# design.net
KiCad netlist of a schematic drawn in Altium Designer
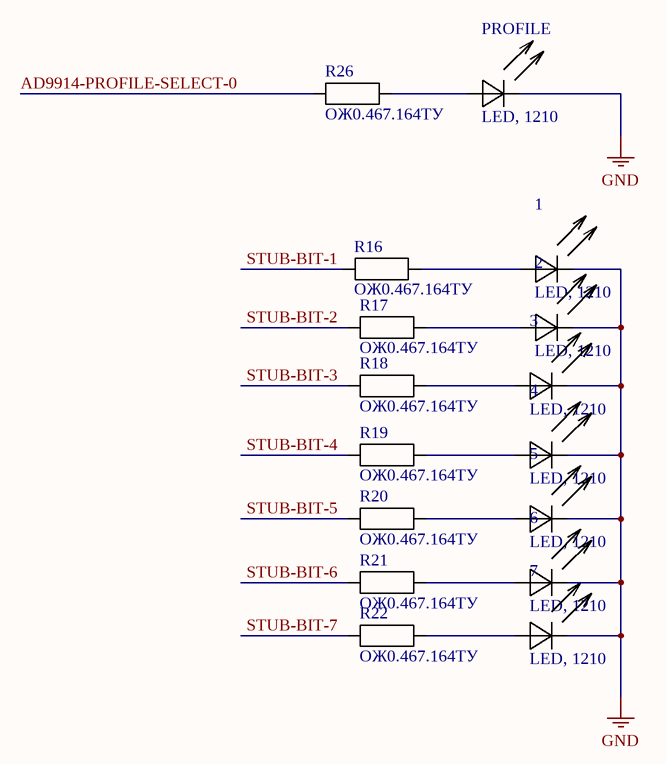
[diagram p0: Светодиоды.SchDoc]

(export (version "E")
  (design (tool "Eeschema 10.0.6"))
  (components
    (comp (ref "1")
      (value "LED, 1210")
      (footprint "PLCC4-1210")
      (fields (field (name "MANUFACTURERPARTNUMBER") "1210 LED"))
      (libsource (lib "ДИОДЫ") (part "1210 LED"))
    )
    (comp (ref "2")
      (value "LED, 1210")
      (footprint "PLCC4-1210")
      (fields (field (name "MANUFACTURERPARTNUMBER") "1210 LED"))
      (libsource (lib "ДИОДЫ") (part "1210 LED"))
    )
    (comp (ref "3")
      (value "LED, 1210")
      (footprint "PLCC4-1210")
      (fields (field (name "MANUFACTURERPARTNUMBER") "1210 LED"))
      (libsource (lib "ДИОДЫ") (part "1210 LED"))
    )
    (comp (ref "4")
      (value "LED, 1210")
      (footprint "PLCC4-1210")
      (fields (field (name "MANUFACTURERPARTNUMBER") "1210 LED"))
      (libsource (lib "ДИОДЫ") (part "1210 LED"))
    )
    (comp (ref "5")
      (value "LED, 1210")
      (footprint "PLCC4-1210")
      (fields (field (name "MANUFACTURERPARTNUMBER") "1210 LED"))
      (libsource (lib "ДИОДЫ") (part "1210 LED"))
    )
    (comp (ref "6")
      (value "LED, 1210")
      (footprint "PLCC4-1210")
      (fields (field (name "MANUFACTURERPARTNUMBER") "1210 LED"))
      (libsource (lib "ДИОДЫ") (part "1210 LED"))
    )
    (comp (ref "7")
      (value "LED, 1210")
      (footprint "PLCC4-1210")
      (fields (field (name "MANUFACTURERPARTNUMBER") "1210 LED"))
      (libsource (lib "ДИОДЫ") (part "1210 LED"))
    )
    (comp (ref "PROFILE")
      (value "LED, 1210")
      (footprint "PLCC4-1210")
      (fields (field (name "MANUFACTURERPARTNUMBER") "1210 LED"))
      (libsource (lib "ДИОДЫ") (part "1210 LED"))
    )
    (comp (ref "R16")
      (value "ОЖ0.467.164ТУ")
      (footprint "Р1-8МП-0,125")
      (fields
        (field (name "TOLERANCE") "±1%-0,5-Л")
        (field (name "MANUFACTURERPARTNUMBER") "Р1-8МП-0,125-100 Ом±1%-0,5-Л")
      )
      (libsource (lib "РЕЗИСТОРЫ") (part "Р1-8МП-0,125-100 Ом±1%"))
    )
    (comp (ref "R17")
      (value "ОЖ0.467.164ТУ")
      (footprint "Р1-8МП-0,125")
      (fields
        (field (name "TOLERANCE") "±1%-0,5-Л")
        (field (name "MANUFACTURERPARTNUMBER") "Р1-8МП-0,125-100 Ом±1%-0,5-Л")
      )
      (libsource (lib "РЕЗИСТОРЫ") (part "Р1-8МП-0,125-100 Ом±1%"))
    )
    (comp (ref "R18")
      (value "ОЖ0.467.164ТУ")
      (footprint "Р1-8МП-0,125")
      (fields
        (field (name "TOLERANCE") "±1%-0,5-Л")
        (field (name "MANUFACTURERPARTNUMBER") "Р1-8МП-0,125-100 Ом±1%-0,5-Л")
      )
      (libsource (lib "РЕЗИСТОРЫ") (part "Р1-8МП-0,125-100 Ом±1%"))
    )
    (comp (ref "R19")
      (value "ОЖ0.467.164ТУ")
      (footprint "Р1-8МП-0,125")
      (fields
        (field (name "TOLERANCE") "±1%-0,5-Л")
        (field (name "MANUFACTURERPARTNUMBER") "Р1-8МП-0,125-100 Ом±1%-0,5-Л")
      )
      (libsource (lib "РЕЗИСТОРЫ") (part "Р1-8МП-0,125-100 Ом±1%"))
    )
    (comp (ref "R20")
      (value "ОЖ0.467.164ТУ")
      (footprint "Р1-8МП-0,125")
      (fields
        (field (name "TOLERANCE") "±1%-0,5-Л")
        (field (name "MANUFACTURERPARTNUMBER") "Р1-8МП-0,125-100 Ом±1%-0,5-Л")
      )
      (libsource (lib "РЕЗИСТОРЫ") (part "Р1-8МП-0,125-100 Ом±1%"))
    )
    (comp (ref "R21")
      (value "ОЖ0.467.164ТУ")
      (footprint "Р1-8МП-0,125")
      (fields
        (field (name "TOLERANCE") "±1%-0,5-Л")
        (field (name "MANUFACTURERPARTNUMBER") "Р1-8МП-0,125-100 Ом±1%-0,5-Л")
      )
      (libsource (lib "РЕЗИСТОРЫ") (part "Р1-8МП-0,125-100 Ом±1%"))
    )
    (comp (ref "R22")
      (value "ОЖ0.467.164ТУ")
      (footprint "Р1-8МП-0,125")
      (fields
        (field (name "TOLERANCE") "±1%-0,5-Л")
        (field (name "MANUFACTURERPARTNUMBER") "Р1-8МП-0,125-100 Ом±1%-0,5-Л")
      )
      (libsource (lib "РЕЗИСТОРЫ") (part "Р1-8МП-0,125-100 Ом±1%"))
    )
    (comp (ref "R26")
      (value "ОЖ0.467.164ТУ")
      (footprint "Р1-8МП-0,125")
      (fields
        (field (name "TOLERANCE") "±1%-0,5-Л")
        (field (name "MANUFACTURERPARTNUMBER") "Р1-8МП-0,125-100 Ом±1%-0,5-Л")
      )
      (libsource (lib "РЕЗИСТОРЫ") (part "Р1-8МП-0,125-100 Ом±1%"))
    )
  )
  (nets
    (net (code "1") (name "/AD9914-PROFILE-SELECT-0") (class "Default")
      (node (ref "R26") (pin "1") (pinfunction "1_1") (pintype "passive"))
    )
    (net (code "2") (name "/STUB-BIT-1") (class "Default")
      (node (ref "R16") (pin "1") (pinfunction "1_1") (pintype "passive"))
    )
    (net (code "3") (name "/STUB-BIT-2") (class "Default")
      (node (ref "R17") (pin "1") (pinfunction "1_1") (pintype "passive"))
    )
    (net (code "4") (name "/STUB-BIT-3") (class "Default")
      (node (ref "R18") (pin "1") (pinfunction "1_1") (pintype "passive"))
    )
    (net (code "5") (name "/STUB-BIT-4") (class "Default")
      (node (ref "R19") (pin "1") (pinfunction "1_1") (pintype "passive"))
    )
    (net (code "6") (name "/STUB-BIT-5") (class "Default")
      (node (ref "R20") (pin "1") (pinfunction "1_1") (pintype "passive"))
    )
    (net (code "7") (name "/STUB-BIT-6") (class "Default")
      (node (ref "R21") (pin "1") (pinfunction "1_1") (pintype "passive"))
    )
    (net (code "8") (name "/STUB-BIT-7") (class "Default")
      (node (ref "R22") (pin "1") (pinfunction "1_1") (pintype "passive"))
    )
    (net (code "9") (name "GND") (class "Default")
      (node (ref "1") (pin "2") (pinfunction "2_2") (pintype "passive"))
      (node (ref "2") (pin "2") (pinfunction "2_2") (pintype "passive"))
      (node (ref "3") (pin "2") (pinfunction "2_2") (pintype "passive"))
      (node (ref "4") (pin "2") (pinfunction "2_2") (pintype "passive"))
      (node (ref "5") (pin "2") (pinfunction "2_2") (pintype "passive"))
      (node (ref "6") (pin "2") (pinfunction "2_2") (pintype "passive"))
      (node (ref "7") (pin "2") (pinfunction "2_2") (pintype "passive"))
      (node (ref "PROFILE") (pin "2") (pinfunction "2_2") (pintype "passive"))
    )
    (net (code "10") (name "Net-(1-Pad1)") (class "Default")
      (node (ref "1") (pin "1") (pinfunction "1_1") (pintype "passive"))
      (node (ref "R16") (pin "2") (pinfunction "2_2") (pintype "passive"))
    )
    (net (code "11") (name "Net-(2-Pad1)") (class "Default")
      (node (ref "2") (pin "1") (pinfunction "1_1") (pintype "passive"))
      (node (ref "R17") (pin "2") (pinfunction "2_2") (pintype "passive"))
    )
    (net (code "12") (name "Net-(3-Pad1)") (class "Default")
      (node (ref "3") (pin "1") (pinfunction "1_1") (pintype "passive"))
      (node (ref "R18") (pin "2") (pinfunction "2_2") (pintype "passive"))
    )
    (net (code "13") (name "Net-(4-Pad1)") (class "Default")
      (node (ref "4") (pin "1") (pinfunction "1_1") (pintype "passive"))
      (node (ref "R19") (pin "2") (pinfunction "2_2") (pintype "passive"))
    )
    (net (code "14") (name "Net-(5-Pad1)") (class "Default")
      (node (ref "5") (pin "1") (pinfunction "1_1") (pintype "passive"))
      (node (ref "R20") (pin "2") (pinfunction "2_2") (pintype "passive"))
    )
    (net (code "15") (name "Net-(6-Pad1)") (class "Default")
      (node (ref "6") (pin "1") (pinfunction "1_1") (pintype "passive"))
      (node (ref "R21") (pin "2") (pinfunction "2_2") (pintype "passive"))
    )
    (net (code "16") (name "Net-(7-Pad1)") (class "Default")
      (node (ref "7") (pin "1") (pinfunction "1_1") (pintype "passive"))
      (node (ref "R22") (pin "2") (pinfunction "2_2") (pintype "passive"))
    )
    (net (code "17") (name "Net-(PROFILE-Pad1)") (class "Default")
      (node (ref "PROFILE") (pin "1") (pinfunction "1_1") (pintype "passive"))
      (node (ref "R26") (pin "2") (pinfunction "2_2") (pintype "passive"))
    )
  )
)
